# Schem_Vehicle_Tracking_System.net
KiCad netlist of a schematic drawn in EasyEDA
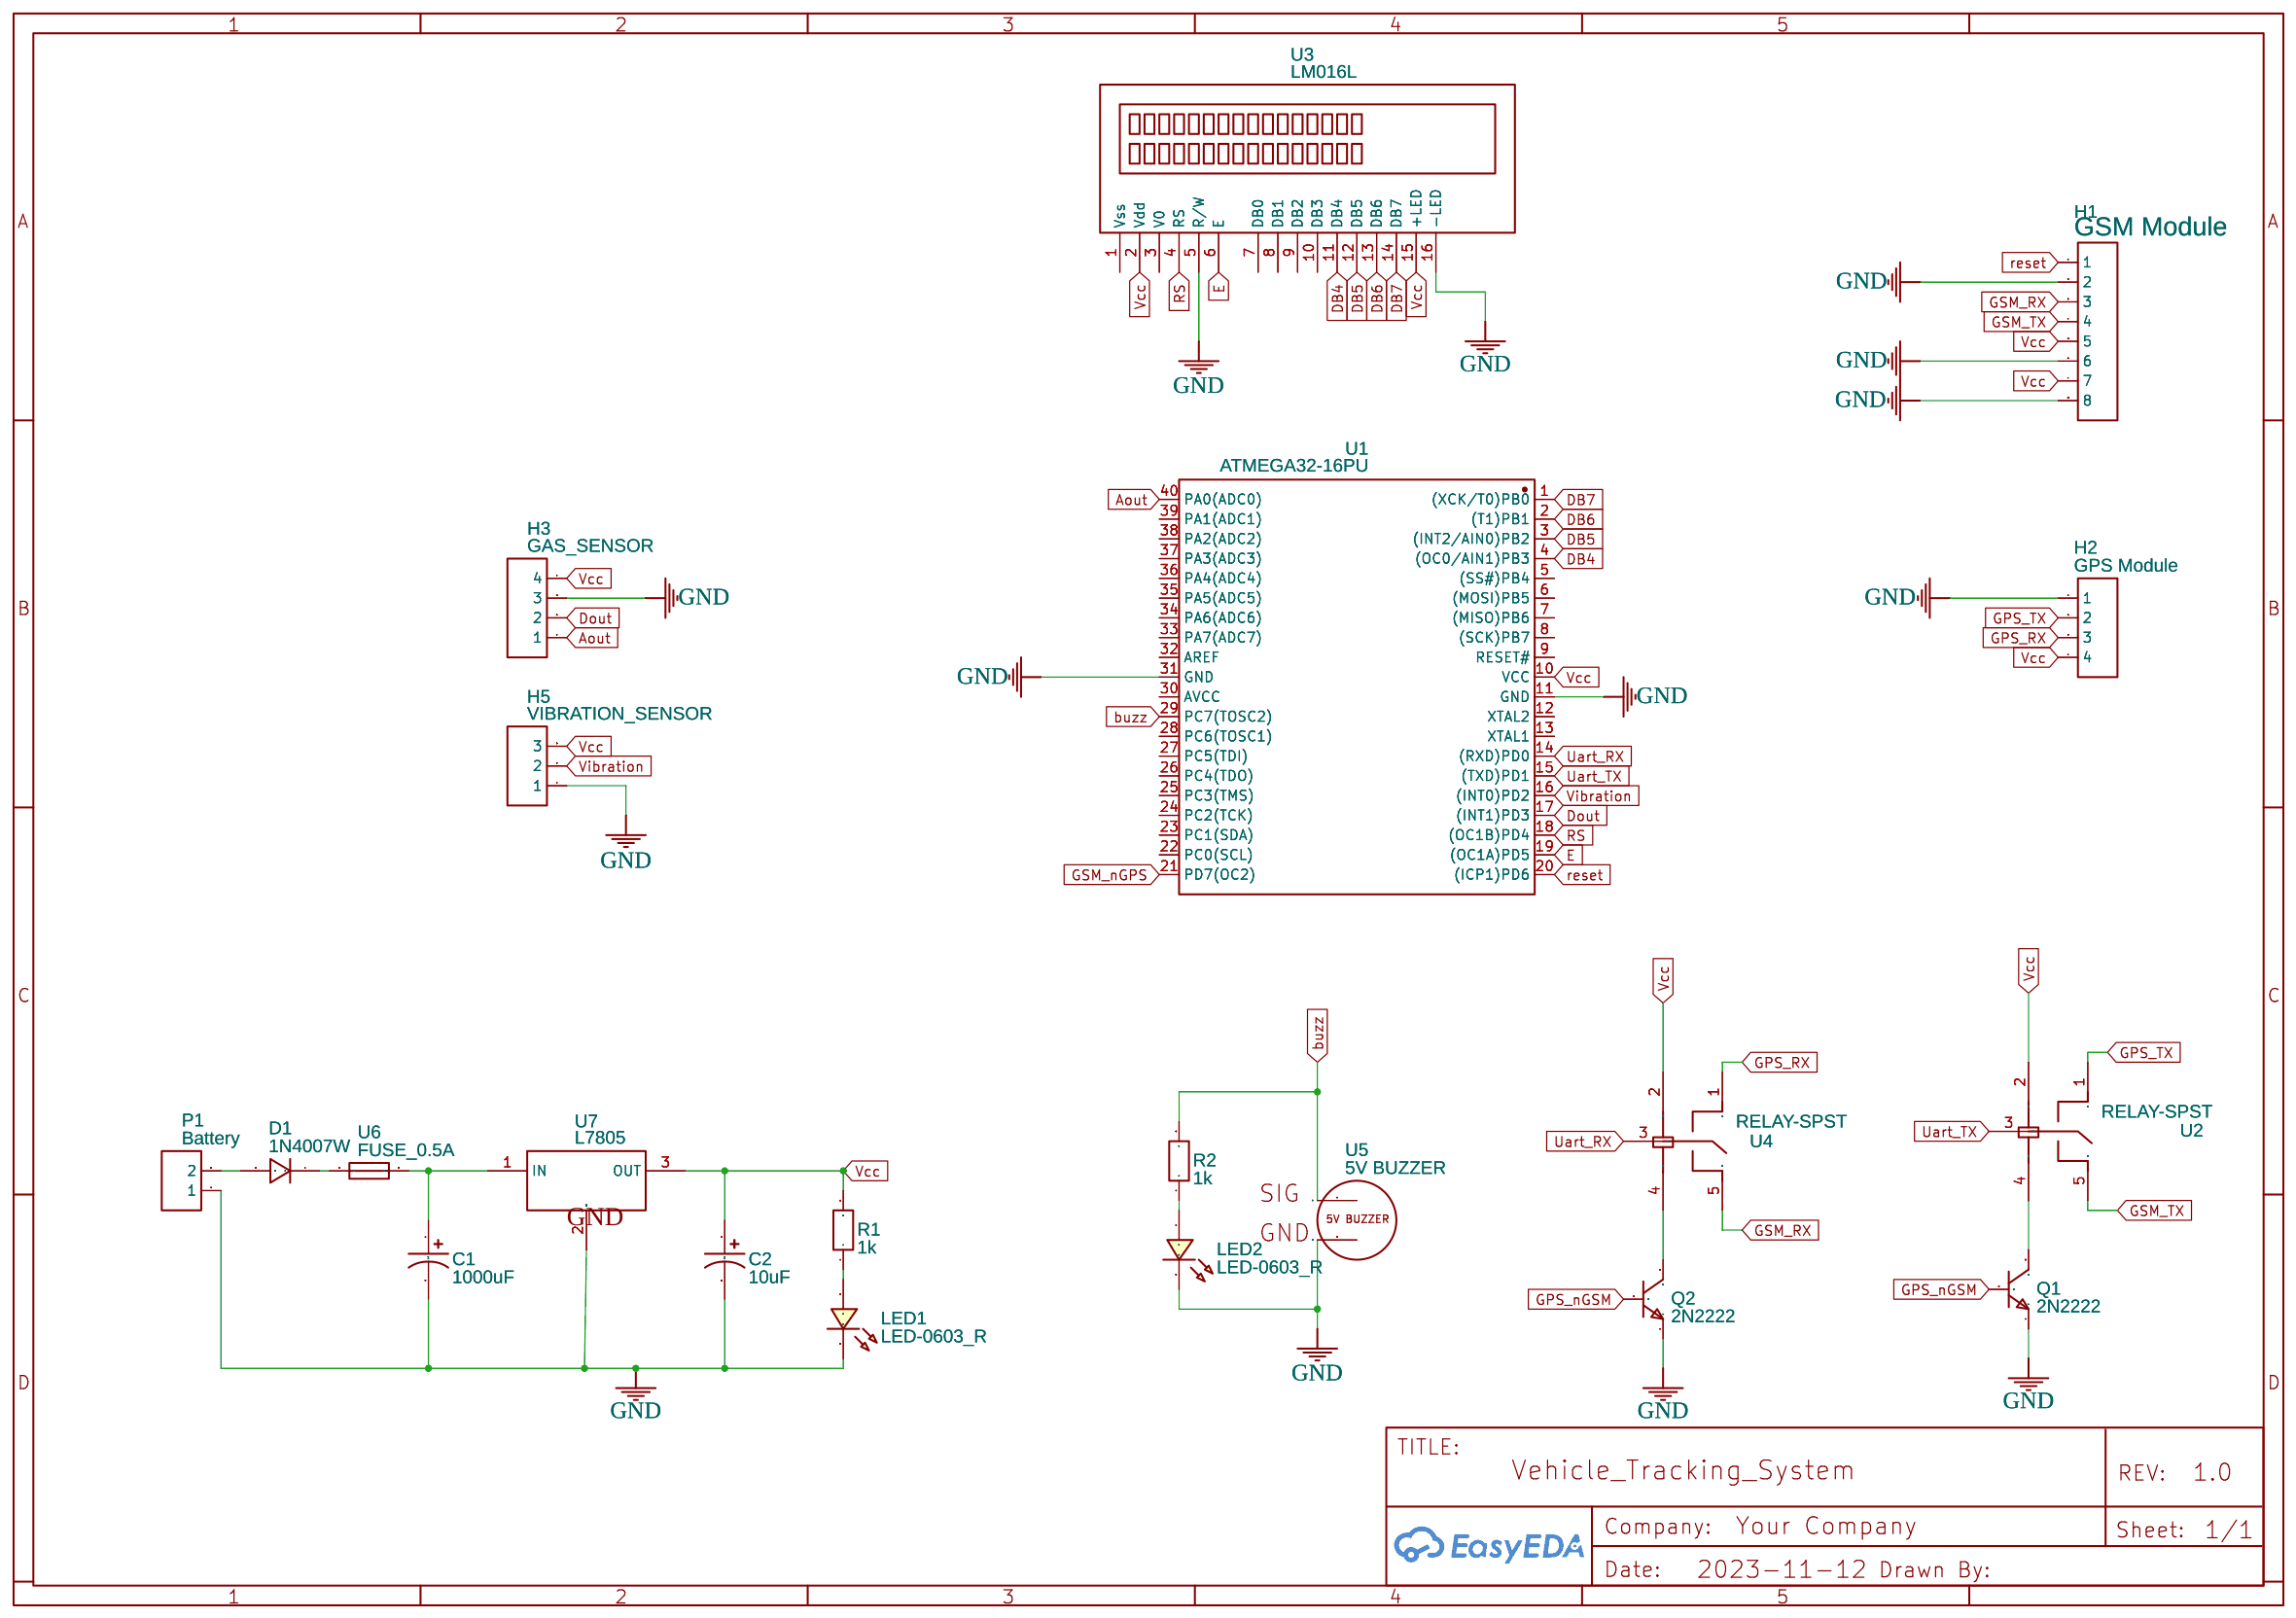
[diagram p0: schematic sheet]

(export (version "E")
  (design (tool "Eeschema 10.0.6"))
  (components
    (comp (ref "C1") (value "1000uF") (libsource (lib "") (part "C_Tan_SMD_A_US")))
    (comp (ref "C2") (value "10uF") (libsource (lib "") (part "C_Tan_SMD_A_US_1")))
    (comp (ref "D1")
      (value "1N4007W")
      (fields (field (name "Manufacturer") "BLUE ROCKET"))
      (libsource (lib "") (part "1N4007W"))
    )
    (comp (ref "H1") (value "GSM Module") (libsource (lib "") (part "HDR-F-2.54_1x8")))
    (comp (ref "H2") (value "GPS Module") (libsource (lib "") (part "HDR-F-2.54_1x4_1")))
    (comp (ref "H3") (value "GAS_SENSOR") (libsource (lib "") (part "HDR-F-2.54_1x4")))
    (comp (ref "H5") (value "VIBRATION_SENSOR") (libsource (lib "") (part "HDR-F-2.54_1x3")))
    (comp (ref "LED1")
      (value "LED-0603_R")
      (fields
        (field (name "Manufacturer Part") "19-217/R6C-AL1M2VY/3T")
        (field (name "Manufacturer") "EVERLIGHT(台湾亿光)")
      )
      (libsource (lib "") (part "LED-0603_R"))
    )
    (comp (ref "LED2")
      (value "LED-0603_R")
      (fields
        (field (name "Manufacturer Part") "19-217/R6C-AL1M2VY/3T")
        (field (name "Manufacturer") "EVERLIGHT(台湾亿光)")
      )
      (libsource (lib "") (part "LED-0603_R"))
    )
    (comp (ref "P1") (value "Battery") (libsource (lib "") (part "HDR-F-2.54_1x2")))
    (comp (ref "Q1")
      (value "2N2222")
      (fields (field (name "Manufacturer Part") "2N2222A") (field (name "Manufacturer") "ST(先科)"))
      (libsource (lib "") (part "2N2222"))
    )
    (comp (ref "Q2")
      (value "2N2222")
      (fields (field (name "Manufacturer Part") "2N2222A") (field (name "Manufacturer") "ST(先科)"))
      (libsource (lib "") (part "2N2222"))
    )
    (comp (ref "R1") (value "1k") (libsource (lib "") (part "R_0603_EU")))
    (comp (ref "R2") (value "1k") (libsource (lib "") (part "R_0603_EU")))
    (comp (ref "U1")
      (value "ATMEGA32-16PU")
      (fields (field (name "Manufacturer") "MICROCHIP(美国微芯)"))
      (libsource (lib "") (part "ATMEGA32-16PU"))
    )
    (comp (ref "U2")
      (value "RELAY-SPST")
      (fields (field (name "Manufacturer Part") "Relay-SPST"))
      (libsource (lib "") (part "RELAY-SPST"))
    )
    (comp (ref "U3")
      (value "LM016L")
      (fields (field (name "Manufacturer Part") "LCD LM016L 16x2"))
      (libsource (lib "") (part "LM016L"))
    )
    (comp (ref "U4")
      (value "RELAY-SPST")
      (fields (field (name "Manufacturer Part") "Relay-SPST"))
      (libsource (lib "") (part "RELAY-SPST"))
    )
    (comp (ref "U5") (value "5V BUZZER") (libsource (lib "") (part "5V BUZZER")))
    (comp (ref "U6")
      (value "FUSE_0.5A")
      (fields (field (name "Manufacturer Part") "Fuse_0.5A"))
      (libsource (lib "") (part "FUSE_0.5A"))
    )
    (comp (ref "U7")
      (value "L7805")
      (fields (field (name "Manufacturer") "SY(顺烨）"))
      (libsource (lib "") (part "L7805"))
    )
  )
  (nets
    (net (code "1") (name "Aout") (class "Default")
      (node (ref "H3") (pin "1") (pinfunction "1_1") (pintype "unspecified"))
      (node (ref "U1") (pin "40") (pinfunction "PA0(ADC0)_40") (pintype "unspecified"))
    )
    (net (code "2") (name "DB4") (class "Default")
      (node (ref "U1") (pin "4") (pinfunction "(OC0/AIN1)PB3_4") (pintype "unspecified"))
      (node (ref "U3") (pin "11") (pinfunction "DB4_11") (pintype "unspecified"))
    )
    (net (code "3") (name "DB5") (class "Default")
      (node (ref "U1") (pin "3") (pinfunction "(INT2/AIN0)PB2_3") (pintype "unspecified"))
      (node (ref "U3") (pin "12") (pinfunction "DB5_12") (pintype "unspecified"))
    )
    (net (code "4") (name "DB6") (class "Default")
      (node (ref "U1") (pin "2") (pinfunction "(T1)PB1_2") (pintype "unspecified"))
      (node (ref "U3") (pin "13") (pinfunction "DB6_13") (pintype "unspecified"))
    )
    (net (code "5") (name "DB7") (class "Default")
      (node (ref "U1") (pin "1") (pinfunction "(XCK/T0)PB0_1") (pintype "unspecified"))
      (node (ref "U3") (pin "14") (pinfunction "DB7_14") (pintype "unspecified"))
    )
    (net (code "6") (name "Dout") (class "Default")
      (node (ref "H3") (pin "2") (pinfunction "2_2") (pintype "unspecified"))
      (node (ref "U1") (pin "17") (pinfunction "(INT1)PD3_17") (pintype "unspecified"))
    )
    (net (code "7") (name "E") (class "Default")
      (node (ref "U1") (pin "19") (pinfunction "(OC1A)PD5_19") (pintype "unspecified"))
      (node (ref "U3") (pin "6") (pinfunction "E_6") (pintype "unspecified"))
    )
    (net (code "8") (name "GND") (class "Default")
      (node (ref "C1") (pin "2") (pinfunction "2_2") (pintype "unspecified"))
      (node (ref "C2") (pin "2") (pinfunction "2_2") (pintype "unspecified"))
      (node (ref "H1") (pin "2") (pinfunction "2_2") (pintype "unspecified"))
      (node (ref "H1") (pin "6") (pinfunction "6_6") (pintype "unspecified"))
      (node (ref "H1") (pin "8") (pinfunction "8_8") (pintype "unspecified"))
      (node (ref "H2") (pin "1") (pinfunction "1_1") (pintype "unspecified"))
      (node (ref "H3") (pin "3") (pinfunction "3_3") (pintype "unspecified"))
      (node (ref "H5") (pin "1") (pinfunction "1_1") (pintype "input"))
      (node (ref "LED1") (pin "2") (pinfunction "2_2") (pintype "unspecified"))
      (node (ref "LED2") (pin "2") (pinfunction "2_2") (pintype "unspecified"))
      (node (ref "P1") (pin "1") (pinfunction "1_1") (pintype "input"))
      (node (ref "Q1") (pin "1") (pinfunction "E_1") (pintype "unspecified"))
      (node (ref "Q2") (pin "1") (pinfunction "E_1") (pintype "unspecified"))
      (node (ref "U1") (pin "11") (pinfunction "GND_11") (pintype "unspecified"))
      (node (ref "U1") (pin "31") (pinfunction "GND_31") (pintype "unspecified"))
      (node (ref "U3") (pin "16") (pinfunction "-LED_16") (pintype "unspecified"))
      (node (ref "U3") (pin "5") (pinfunction "R/W_5") (pintype "unspecified"))
      (node (ref "U7") (pin "2") (pinfunction "GND_2") (pintype "passive"))
    )
    (net (code "9") (name "GPS_RX") (class "Default")
      (node (ref "H2") (pin "3") (pinfunction "3_3") (pintype "unspecified"))
      (node (ref "U4") (pin "1") (pinfunction "1_1") (pintype "unspecified"))
    )
    (net (code "10") (name "GPS_TX") (class "Default")
      (node (ref "H2") (pin "2") (pinfunction "2_2") (pintype "unspecified"))
      (node (ref "U2") (pin "1") (pinfunction "1_1") (pintype "unspecified"))
    )
    (net (code "11") (name "GPS_nGSM") (class "Default")
      (node (ref "Q1") (pin "2") (pinfunction "B_2") (pintype "unspecified"))
      (node (ref "Q2") (pin "2") (pinfunction "B_2") (pintype "unspecified"))
    )
    (net (code "12") (name "GSM_RX") (class "Default")
      (node (ref "H1") (pin "3") (pinfunction "3_3") (pintype "unspecified"))
      (node (ref "U4") (pin "5") (pinfunction "5_5") (pintype "unspecified"))
    )
    (net (code "13") (name "GSM_TX") (class "Default")
      (node (ref "H1") (pin "4") (pinfunction "4_4") (pintype "unspecified"))
      (node (ref "U2") (pin "5") (pinfunction "5_5") (pintype "unspecified"))
    )
    (net (code "14") (name "GSM_nGPS") (class "Default")
      (node (ref "U1") (pin "21") (pinfunction "PD7(OC2)_21") (pintype "unspecified"))
    )
    (net (code "15") (name "Net-(D1-Pad1)") (class "Default")
      (node (ref "D1") (pin "1") (pinfunction "1_1") (pintype "unspecified"))
      (node (ref "U6") (pin "1") (pinfunction "1_1") (pintype "unspecified"))
    )
    (net (code "16") (name "Net-(D1-Pad2)") (class "Default")
      (node (ref "D1") (pin "2") (pinfunction "2_2") (pintype "unspecified"))
      (node (ref "P1") (pin "2") (pinfunction "2_2") (pintype "input"))
    )
    (net (code "17") (name "Net-(LED1-Pad1)") (class "Default")
      (node (ref "LED1") (pin "1") (pinfunction "1_1") (pintype "unspecified"))
      (node (ref "R1") (pin "1") (pinfunction "1_1") (pintype "unspecified"))
    )
    (net (code "18") (name "Net-(LED2-Pad1)") (class "Default")
      (node (ref "LED2") (pin "1") (pinfunction "1_1") (pintype "unspecified"))
      (node (ref "R2") (pin "1") (pinfunction "1_1") (pintype "unspecified"))
    )
    (net (code "19") (name "Net-(Q1-C)") (class "Default")
      (node (ref "Q1") (pin "3") (pinfunction "C_3") (pintype "unspecified"))
      (node (ref "U2") (pin "4") (pinfunction "4_4") (pintype "unspecified"))
    )
    (net (code "20") (name "Net-(Q2-C)") (class "Default")
      (node (ref "Q2") (pin "3") (pinfunction "C_3") (pintype "unspecified"))
      (node (ref "U4") (pin "4") (pinfunction "4_4") (pintype "unspecified"))
    )
    (net (code "21") (name "Net-(U7-IN)") (class "Default")
      (node (ref "C1") (pin "1") (pinfunction "1_1") (pintype "unspecified"))
      (node (ref "U6") (pin "2") (pinfunction "2_2") (pintype "unspecified"))
      (node (ref "U7") (pin "1") (pinfunction "IN_1") (pintype "passive"))
    )
    (net (code "22") (name "RS") (class "Default")
      (node (ref "U1") (pin "18") (pinfunction "(OC1B)PD4_18") (pintype "unspecified"))
      (node (ref "U3") (pin "4") (pinfunction "RS_4") (pintype "unspecified"))
    )
    (net (code "23") (name "Uart_RX") (class "Default")
      (node (ref "U1") (pin "14") (pinfunction "(RXD)PD0_14") (pintype "unspecified"))
      (node (ref "U4") (pin "3") (pinfunction "3_3") (pintype "unspecified"))
    )
    (net (code "24") (name "Uart_TX") (class "Default")
      (node (ref "U1") (pin "15") (pinfunction "(TXD)PD1_15") (pintype "unspecified"))
      (node (ref "U2") (pin "3") (pinfunction "3_3") (pintype "unspecified"))
    )
    (net (code "25") (name "Vcc") (class "Default")
      (node (ref "C2") (pin "1") (pinfunction "1_1") (pintype "unspecified"))
      (node (ref "H1") (pin "5") (pinfunction "5_5") (pintype "unspecified"))
      (node (ref "H1") (pin "7") (pinfunction "7_7") (pintype "unspecified"))
      (node (ref "H2") (pin "4") (pinfunction "4_4") (pintype "unspecified"))
      (node (ref "H3") (pin "4") (pinfunction "4_4") (pintype "unspecified"))
      (node (ref "H5") (pin "3") (pinfunction "3_3") (pintype "input"))
      (node (ref "R1") (pin "2") (pinfunction "2_2") (pintype "unspecified"))
      (node (ref "U1") (pin "10") (pinfunction "VCC_10") (pintype "unspecified"))
      (node (ref "U2") (pin "2") (pinfunction "2_2") (pintype "unspecified"))
      (node (ref "U3") (pin "15") (pinfunction "+LED_15") (pintype "unspecified"))
      (node (ref "U3") (pin "2") (pinfunction "Vdd_2") (pintype "unspecified"))
      (node (ref "U4") (pin "2") (pinfunction "2_2") (pintype "unspecified"))
      (node (ref "U7") (pin "3") (pinfunction "OUT_3") (pintype "passive"))
    )
    (net (code "26") (name "Vibration") (class "Default")
      (node (ref "H5") (pin "2") (pinfunction "2_2") (pintype "input"))
      (node (ref "U1") (pin "16") (pinfunction "(INT0)PD2_16") (pintype "unspecified"))
    )
    (net (code "27") (name "buzz") (class "Default")
      (node (ref "R2") (pin "2") (pinfunction "2_2") (pintype "unspecified"))
      (node (ref "U1") (pin "29") (pinfunction "PC7(TOSC2)_29") (pintype "unspecified"))
    )
    (net (code "28") (name "reset") (class "Default")
      (node (ref "H1") (pin "1") (pinfunction "1_1") (pintype "unspecified"))
      (node (ref "U1") (pin "20") (pinfunction "(ICP1)PD6_20") (pintype "unspecified"))
    )
    (net (code "29") (name "unconnected-(U1-(MISO)PB6-Pad7)") (class "Default")
      (node (ref "U1") (pin "7") (pinfunction "(MISO)PB6_7") (pintype "unspecified"))
    )
    (net (code "30") (name "unconnected-(U1-(MOSI)PB5-Pad6)") (class "Default")
      (node (ref "U1") (pin "6") (pinfunction "(MOSI)PB5_6") (pintype "unspecified"))
    )
    (net (code "31") (name "unconnected-(U1-(SCK)PB7-Pad8)") (class "Default")
      (node (ref "U1") (pin "8") (pinfunction "(SCK)PB7_8") (pintype "unspecified"))
    )
    (net (code "32") (name "unconnected-(U1-(SS#)PB4-Pad5)") (class "Default")
      (node (ref "U1") (pin "5") (pinfunction "(SS#)PB4_5") (pintype "unspecified"))
    )
    (net (code "33") (name "unconnected-(U1-AREF-Pad32)") (class "Default")
      (node (ref "U1") (pin "32") (pinfunction "AREF_32") (pintype "unspecified"))
    )
    (net (code "34") (name "unconnected-(U1-AVCC-Pad30)") (class "Default")
      (node (ref "U1") (pin "30") (pinfunction "AVCC_30") (pintype "unspecified"))
    )
    (net (code "35") (name "unconnected-(U1-PA1(ADC1)-Pad39)") (class "Default")
      (node (ref "U1") (pin "39") (pinfunction "PA1(ADC1)_39") (pintype "unspecified"))
    )
    (net (code "36") (name "unconnected-(U1-PA2(ADC2)-Pad38)") (class "Default")
      (node (ref "U1") (pin "38") (pinfunction "PA2(ADC2)_38") (pintype "unspecified"))
    )
    (net (code "37") (name "unconnected-(U1-PA3(ADC3)-Pad37)") (class "Default")
      (node (ref "U1") (pin "37") (pinfunction "PA3(ADC3)_37") (pintype "unspecified"))
    )
    (net (code "38") (name "unconnected-(U1-PA4(ADC4)-Pad36)") (class "Default")
      (node (ref "U1") (pin "36") (pinfunction "PA4(ADC4)_36") (pintype "unspecified"))
    )
    (net (code "39") (name "unconnected-(U1-PA5(ADC5)-Pad35)") (class "Default")
      (node (ref "U1") (pin "35") (pinfunction "PA5(ADC5)_35") (pintype "unspecified"))
    )
    (net (code "40") (name "unconnected-(U1-PA6(ADC6)-Pad34)") (class "Default")
      (node (ref "U1") (pin "34") (pinfunction "PA6(ADC6)_34") (pintype "unspecified"))
    )
    (net (code "41") (name "unconnected-(U1-PA7(ADC7)-Pad33)") (class "Default")
      (node (ref "U1") (pin "33") (pinfunction "PA7(ADC7)_33") (pintype "unspecified"))
    )
    (net (code "42") (name "unconnected-(U1-PC0(SCL)-Pad22)") (class "Default")
      (node (ref "U1") (pin "22") (pinfunction "PC0(SCL)_22") (pintype "unspecified"))
    )
    (net (code "43") (name "unconnected-(U1-PC1(SDA)-Pad23)") (class "Default")
      (node (ref "U1") (pin "23") (pinfunction "PC1(SDA)_23") (pintype "unspecified"))
    )
    (net (code "44") (name "unconnected-(U1-PC2(TCK)-Pad24)") (class "Default")
      (node (ref "U1") (pin "24") (pinfunction "PC2(TCK)_24") (pintype "unspecified"))
    )
    (net (code "45") (name "unconnected-(U1-PC3(TMS)-Pad25)") (class "Default")
      (node (ref "U1") (pin "25") (pinfunction "PC3(TMS)_25") (pintype "unspecified"))
    )
    (net (code "46") (name "unconnected-(U1-PC4(TDO)-Pad26)") (class "Default")
      (node (ref "U1") (pin "26") (pinfunction "PC4(TDO)_26") (pintype "unspecified"))
    )
    (net (code "47") (name "unconnected-(U1-PC5(TDI)-Pad27)") (class "Default")
      (node (ref "U1") (pin "27") (pinfunction "PC5(TDI)_27") (pintype "unspecified"))
    )
    (net (code "48") (name "unconnected-(U1-PC6(TOSC1)-Pad28)") (class "Default")
      (node (ref "U1") (pin "28") (pinfunction "PC6(TOSC1)_28") (pintype "unspecified"))
    )
    (net (code "49") (name "unconnected-(U1-RESET#-Pad9)") (class "Default")
      (node (ref "U1") (pin "9") (pinfunction "RESET#_9") (pintype "unspecified"))
    )
    (net (code "50") (name "unconnected-(U1-XTAL1-Pad13)") (class "Default")
      (node (ref "U1") (pin "13") (pinfunction "XTAL1_13") (pintype "unspecified"))
    )
    (net (code "51") (name "unconnected-(U1-XTAL2-Pad12)") (class "Default")
      (node (ref "U1") (pin "12") (pinfunction "XTAL2_12") (pintype "unspecified"))
    )
    (net (code "52") (name "unconnected-(U3-DB0-Pad7)") (class "Default")
      (node (ref "U3") (pin "7") (pinfunction "DB0_7") (pintype "unspecified"))
    )
    (net (code "53") (name "unconnected-(U3-DB1-Pad8)") (class "Default")
      (node (ref "U3") (pin "8") (pinfunction "DB1_8") (pintype "unspecified"))
    )
    (net (code "54") (name "unconnected-(U3-DB2-Pad9)") (class "Default")
      (node (ref "U3") (pin "9") (pinfunction "DB2_9") (pintype "unspecified"))
    )
    (net (code "55") (name "unconnected-(U3-DB3-Pad10)") (class "Default")
      (node (ref "U3") (pin "10") (pinfunction "DB3_10") (pintype "unspecified"))
    )
    (net (code "56") (name "unconnected-(U3-V0-Pad3)") (class "Default")
      (node (ref "U3") (pin "3") (pinfunction "V0_3") (pintype "unspecified"))
    )
    (net (code "57") (name "unconnected-(U3-Vss-Pad1)") (class "Default")
      (node (ref "U3") (pin "1") (pinfunction "Vss_1") (pintype "unspecified"))
    )
    (net (code "58") (name "unconnected-(U5-Pad1)") (class "Default")
      (node (ref "U5") (pin "1") (pinfunction "1_1") (pintype "unspecified"))
    )
    (net (code "59") (name "unconnected-(U5-Pad2)") (class "Default")
      (node (ref "U5") (pin "2") (pinfunction "2_2") (pintype "unspecified"))
    )
  )
)
